# FullBridge.net
KiCad netlist of a schematic drawn in Altium Designer
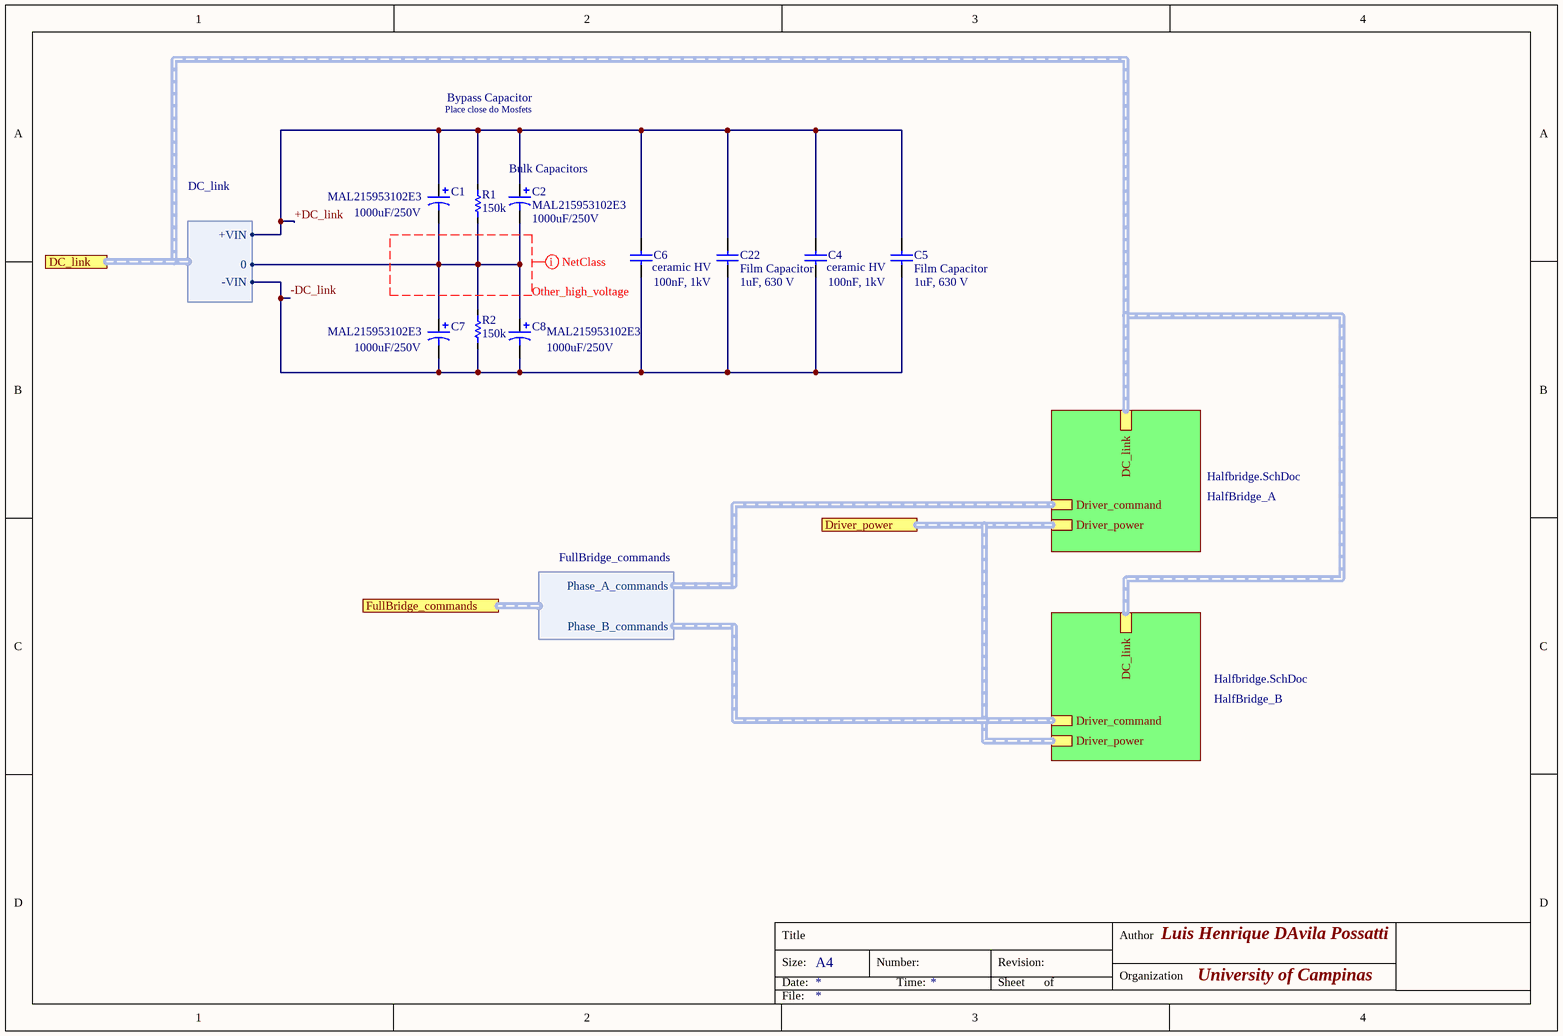
[diagram p0: FullBridge.SchDoc]

(export (version "E")
  (design (tool "Eeschema 10.0.6"))
  (components
    (comp (ref "C1")
      (value "MAL215953102E3")
      (footprint "Radial 35D40H10P")
      (description "Aluminum Electrolytic Capacitor 1000UF 20% 250V SNAP")
      (fields (field (name "ALTIUM_VALUE") "1000uF/250V"))
      (libsource (lib "EdgeInverter_library") (part "MAL215953102E3"))
    )
    (comp (ref "C2")
      (value "MAL215953102E3")
      (footprint "Radial 35D40H10P")
      (description "Aluminum Electrolytic Capacitor 1000UF 20% 250V SNAP")
      (fields (field (name "ALTIUM_VALUE") "1000uF/250V"))
      (libsource (lib "EdgeInverter_library") (part "MAL215953102E3"))
    )
    (comp (ref "C4")
      (value "ceramic HV")
      (footprint "CAPACITOR 1812")
      (description "High Voltage Ceramic SMD capacitor, two part numbers, 100nF")
      (fields (field (name "ALTIUM_VALUE") "100nF, 1kV"))
      (libsource (lib "EdgeInverter_library") (part "Capacitor ceramic High Voltage"))
    )
    (comp (ref "C5")
      (value "Film Capacitor")
      (footprint "MIXED Film Capacitors")
      (description "Metalized Film Capacitor, two part numbers")
      (fields (field (name "ALTIUM_VALUE") "1uF, 630 V"))
      (libsource (lib "EdgeInverter_library") (part "Capacitor Metalized Film"))
    )
    (comp (ref "C6")
      (value "ceramic HV")
      (footprint "CAPACITOR 1812")
      (description "High Voltage Ceramic SMD capacitor, two part numbers, 100nF")
      (fields (field (name "ALTIUM_VALUE") "100nF, 1kV"))
      (libsource (lib "EdgeInverter_library") (part "Capacitor ceramic High Voltage"))
    )
    (comp (ref "C7")
      (value "MAL215953102E3")
      (footprint "Radial 35D40H10P")
      (description "Aluminum Electrolytic Capacitor 1000UF 20% 250V SNAP")
      (fields (field (name "ALTIUM_VALUE") "1000uF/250V"))
      (libsource (lib "EdgeInverter_library") (part "MAL215953102E3"))
    )
    (comp (ref "C8")
      (value "MAL215953102E3")
      (footprint "Radial 35D40H10P")
      (description "Aluminum Electrolytic Capacitor 1000UF 20% 250V SNAP")
      (fields (field (name "ALTIUM_VALUE") "1000uF/250V"))
      (libsource (lib "EdgeInverter_library") (part "MAL215953102E3"))
    )
    (comp (ref "C22")
      (value "Film Capacitor")
      (footprint "MIXED Film Capacitors")
      (description "Metalized Film Capacitor, two part numbers")
      (fields (field (name "ALTIUM_VALUE") "1uF, 630 V"))
      (libsource (lib "EdgeInverter_library") (part "Capacitor Metalized Film"))
    )
    (comp (ref "R1")
      (value "150k")
      (footprint "Resistor 2512")
      (description "SMD resistor 2512, 150kOhm")
      (fields (field (name "Comment") "CRCW2512150KFKEG"))
      (libsource (lib "EdgeInverter_library") (part "CRCW2512150KFKEG"))
    )
    (comp (ref "R2")
      (value "150k")
      (footprint "Resistor 2512")
      (description "SMD resistor 2512, 150kOhm")
      (fields (field (name "Comment") "CRCW2512150KFKEG"))
      (libsource (lib "EdgeInverter_library") (part "CRCW2512150KFKEG"))
    )
  )
  (nets
    (net (code "5") (name "/+DC_link") (class "Default")
      (node (ref "C1") (pin "1") (pinfunction "1_1") (pintype "passive"))
      (node (ref "C2") (pin "1") (pinfunction "1_1") (pintype "passive"))
      (node (ref "C22") (pin "1") (pinfunction "1_1") (pintype "passive"))
      (node (ref "C4") (pin "1") (pinfunction "1_1") (pintype "passive"))
      (node (ref "C5") (pin "1") (pinfunction "1_1") (pintype "passive"))
      (node (ref "C6") (pin "1") (pinfunction "1_1") (pintype "passive"))
      (node (ref "R1") (pin "2") (pinfunction "2_2") (pintype "passive"))
    )
    (net (code "6") (name "/-DC_link") (class "Default")
      (node (ref "C22") (pin "2") (pinfunction "2_2") (pintype "passive"))
      (node (ref "C4") (pin "2") (pinfunction "2_2") (pintype "passive"))
      (node (ref "C5") (pin "2") (pinfunction "2_2") (pintype "passive"))
      (node (ref "C6") (pin "2") (pinfunction "2_2") (pintype "passive"))
      (node (ref "C7") (pin "2") (pinfunction "2_2") (pintype "passive"))
      (node (ref "C8") (pin "2") (pinfunction "2_2") (pintype "passive"))
      (node (ref "R2") (pin "1") (pinfunction "1_1") (pintype "passive"))
    )
    (net (code "12") (name "Net-(C1-Pad2)") (class "Default")
      (node (ref "C1") (pin "2") (pinfunction "2_2") (pintype "passive"))
      (node (ref "C2") (pin "2") (pinfunction "2_2") (pintype "passive"))
      (node (ref "C7") (pin "1") (pinfunction "1_1") (pintype "passive"))
      (node (ref "C8") (pin "1") (pinfunction "1_1") (pintype "passive"))
      (node (ref "R1") (pin "1") (pinfunction "1_1") (pintype "passive"))
      (node (ref "R2") (pin "2") (pinfunction "2_2") (pintype "passive"))
    )
  )
)
